# PS_2013v11.net
KiCad netlist of a schematic drawn in EAGLE
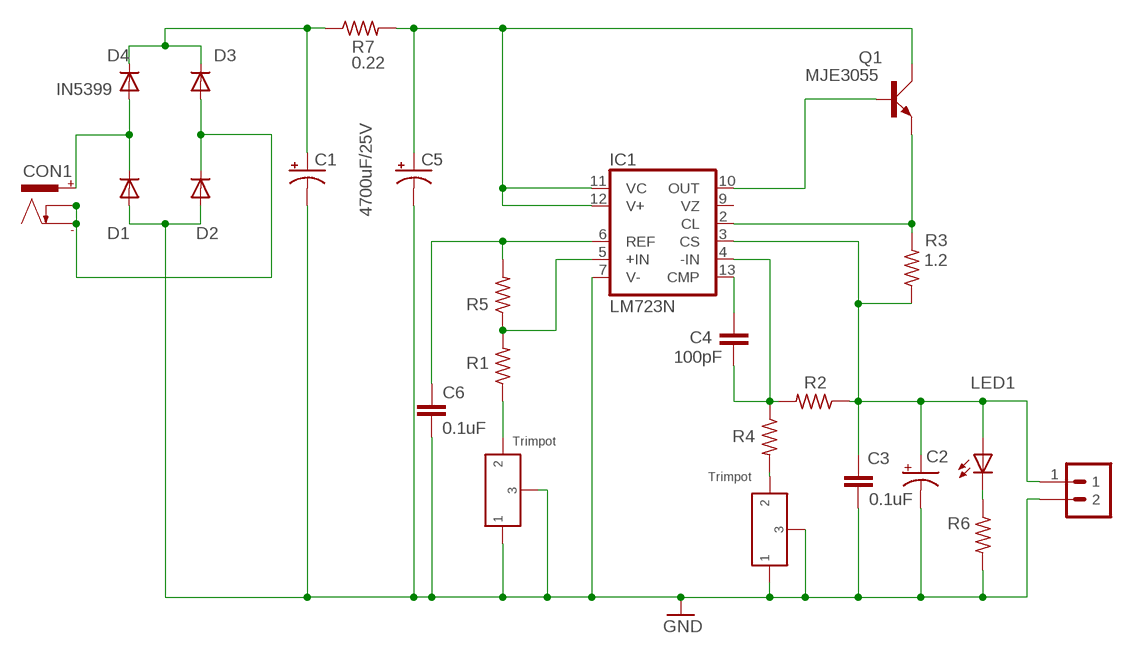
[diagram p0: schematic, sheet 1]

(export (version "E")
  (design (tool "Eeschema 10.0.6"))
  (components
    (comp (ref "C1")
      (value "CPOL-USE7.5-18")
      (footprint "eagle-import:E7,5-18")
      (libsource (lib "eagle-import") (part "CPOL-USE7.5-18"))
    )
    (comp (ref "C2")
      (value "CPOL-USE2,5-6E")
      (footprint "eagle-import:E2,5-6E")
      (libsource (lib "eagle-import") (part "CPOL-USE2,5-6E"))
    )
    (comp (ref "C3")
      (value "0.1uF")
      (footprint "eagle-import:C050-024X044")
      (libsource (lib "eagle-import") (part "C-EU050-024X044"))
    )
    (comp (ref "C4")
      (value "100pF")
      (footprint "eagle-import:C050-024X044")
      (libsource (lib "eagle-import") (part "C-EU050-024X044"))
    )
    (comp (ref "C5")
      (value "4700uF/25V")
      (footprint "eagle-import:E7,5-18")
      (libsource (lib "eagle-import") (part "CPOL-USE7.5-18"))
    )
    (comp (ref "C6")
      (value "0.1uF")
      (footprint "eagle-import:C050-024X044")
      (libsource (lib "eagle-import") (part "C-EU050-024X044"))
    )
    (comp (ref "CON1")
      (value "POWER_CON")
      (footprint "eagle-import:NEB21R")
      (libsource (lib "eagle-import") (part "POWER_CON"))
    )
    (comp (ref "D1")
      (value "IN5399")
      (footprint "eagle-import:DO15-12")
      (libsource (lib "eagle-import") (part "DIODE-DO15-12"))
    )
    (comp (ref "D2")
      (value "IN5399")
      (footprint "eagle-import:DO15-12")
      (libsource (lib "eagle-import") (part "DIODE-DO15-12"))
    )
    (comp (ref "D3")
      (value "IN5399")
      (footprint "eagle-import:DO15-12")
      (libsource (lib "eagle-import") (part "DIODE-DO15-12"))
    )
    (comp (ref "D4")
      (value "IN5399")
      (footprint "eagle-import:DO15-12")
      (libsource (lib "eagle-import") (part "DIODE-DO15-12"))
    )
    (comp (ref "IC1")
      (value "LM723N")
      (footprint "eagle-import:DIL14")
      (libsource (lib "eagle-import") (part "723NLM"))
    )
    (comp (ref "LED1")
      (value "LED3MM")
      (footprint "eagle-import:LED3MM")
      (libsource (lib "eagle-import") (part "LED3MM"))
    )
    (comp (ref "Q1")
      (value "MJE3055")
      (footprint "eagle-import:TO220AV")
      (libsource (lib "eagle-import") (part "MJE3055"))
    )
    (comp (ref "R1")
      (value "560k")
      (footprint "eagle-import:0204_5")
      (libsource (lib "eagle-import") (part "R-US_0204/5"))
    )
    (comp (ref "R2")
      (value "300k")
      (footprint "eagle-import:0204_5")
      (libsource (lib "eagle-import") (part "R-US_0204/5"))
    )
    (comp (ref "R3")
      (value "1.2")
      (footprint "eagle-import:0617_22")
      (libsource (lib "eagle-import") (part "R-US_0617/22"))
    )
    (comp (ref "R4")
      (value "300k")
      (footprint "eagle-import:0204_5")
      (libsource (lib "eagle-import") (part "R-US_0204/5"))
    )
    (comp (ref "R5")
      (value "220k")
      (footprint "eagle-import:0204_5")
      (libsource (lib "eagle-import") (part "R-US_0204/5"))
    )
    (comp (ref "R6")
      (value "330")
      (footprint "eagle-import:0204_5")
      (libsource (lib "eagle-import") (part "R-US_0204/5"))
    )
    (comp (ref "R7")
      (value "0.22")
      (footprint "eagle-import:0617_22")
      (libsource (lib "eagle-import") (part "R-US_0617/22"))
    )
    (comp (ref "U$1")
      (value "PRESET")
      (footprint "eagle-import:PRESET_PACK")
      (libsource (lib "eagle-import") (part "PRESET"))
    )
    (comp (ref "U$3")
      (value "PRESET")
      (footprint "eagle-import:PRESET_PACK")
      (libsource (lib "eagle-import") (part "PRESET"))
    )
    (comp (ref "U$4")
      (value "1X2_LR")
      (footprint "eagle-import:1X2_LR")
      (libsource (lib "eagle-import") (part "1X2_LR"))
    )
  )
  (nets
    (net (code "1") (name "GND") (class "Default")
      (node (ref "C1") (pin "-") (pinfunction "-_-") (pintype "passive"))
      (node (ref "C2") (pin "-") (pinfunction "-_-") (pintype "passive"))
      (node (ref "C3") (pin "2") (pinfunction "2_2") (pintype "passive"))
      (node (ref "C5") (pin "-") (pinfunction "-_-") (pintype "passive"))
      (node (ref "C6") (pin "2") (pinfunction "2_2") (pintype "passive"))
      (node (ref "D1") (pin "A") (pinfunction "A_A") (pintype "passive"))
      (node (ref "D2") (pin "A") (pinfunction "A_A") (pintype "passive"))
      (node (ref "IC1") (pin "7") (pinfunction "V-_7") (pintype "input"))
      (node (ref "R6") (pin "2") (pinfunction "2_2") (pintype "passive"))
      (node (ref "U$1") (pin "P$1") (pinfunction "1_P$1") (pintype "passive"))
      (node (ref "U$1") (pin "P$3") (pinfunction "3_P$3") (pintype "passive"))
      (node (ref "U$3") (pin "P$1") (pinfunction "1_P$1") (pintype "passive"))
      (node (ref "U$3") (pin "P$3") (pinfunction "3_P$3") (pintype "passive"))
      (node (ref "U$4") (pin "2") (pinfunction "2_2") (pintype "passive"))
    )
    (net (code "2") (name "Net-(C1-Pad+)") (class "Default")
      (node (ref "C1") (pin "+") (pinfunction "+_+") (pintype "passive"))
      (node (ref "D3") (pin "C") (pinfunction "C_C") (pintype "passive"))
      (node (ref "D4") (pin "C") (pinfunction "C_C") (pintype "passive"))
      (node (ref "R7") (pin "1") (pinfunction "1_1") (pintype "passive"))
    )
    (net (code "3") (name "Net-(CON1-Pad+)") (class "Default")
      (node (ref "CON1") (pin "+") (pinfunction "+_+") (pintype "passive"))
      (node (ref "D1") (pin "C") (pinfunction "C_C") (pintype "passive"))
      (node (ref "D4") (pin "A") (pinfunction "A_A") (pintype "passive"))
    )
    (net (code "4") (name "Net-(CON1-Pad-)") (class "Default")
      (node (ref "CON1") (pin "-") (pinfunction "-_-") (pintype "passive"))
      (node (ref "CON1") (pin "C") (pinfunction "C_C") (pintype "passive"))
      (node (ref "D2") (pin "C") (pinfunction "C_C") (pintype "passive"))
      (node (ref "D3") (pin "A") (pinfunction "A_A") (pintype "passive"))
    )
    (net (code "5") (name "Net-(IC1-+IN)") (class "Default")
      (node (ref "IC1") (pin "5") (pinfunction "+IN_5") (pintype "input"))
      (node (ref "R1") (pin "2") (pinfunction "2_2") (pintype "passive"))
      (node (ref "R5") (pin "1") (pinfunction "1_1") (pintype "passive"))
    )
    (net (code "6") (name "Net-(IC1--IN)") (class "Default")
      (node (ref "C4") (pin "2") (pinfunction "2_2") (pintype "passive"))
      (node (ref "IC1") (pin "4") (pinfunction "-IN_4") (pintype "input"))
      (node (ref "R2") (pin "2") (pinfunction "2_2") (pintype "passive"))
      (node (ref "R4") (pin "1") (pinfunction "1_1") (pintype "passive"))
    )
    (net (code "7") (name "Net-(IC1-CL)") (class "Default")
      (node (ref "IC1") (pin "2") (pinfunction "CL_2") (pintype "input"))
      (node (ref "Q1") (pin "E") (pinfunction "E_E") (pintype "passive"))
      (node (ref "R3") (pin "2") (pinfunction "2_2") (pintype "passive"))
    )
    (net (code "8") (name "Net-(IC1-CMP)") (class "Default")
      (node (ref "C4") (pin "1") (pinfunction "1_1") (pintype "passive"))
      (node (ref "IC1") (pin "13") (pinfunction "CMP_13") (pintype "passive"))
    )
    (net (code "9") (name "Net-(IC1-CS)") (class "Default")
      (node (ref "C2") (pin "+") (pinfunction "+_+") (pintype "passive"))
      (node (ref "C3") (pin "1") (pinfunction "1_1") (pintype "passive"))
      (node (ref "IC1") (pin "3") (pinfunction "CS_3") (pintype "input"))
      (node (ref "LED1") (pin "A") (pinfunction "A_A") (pintype "passive"))
      (node (ref "R2") (pin "1") (pinfunction "1_1") (pintype "passive"))
      (node (ref "R3") (pin "1") (pinfunction "1_1") (pintype "passive"))
      (node (ref "U$4") (pin "1") (pinfunction "1_1") (pintype "passive"))
    )
    (net (code "10") (name "Net-(IC1-OUT)") (class "Default")
      (node (ref "IC1") (pin "10") (pinfunction "OUT_10") (pintype "output"))
      (node (ref "Q1") (pin "B") (pinfunction "B_B") (pintype "passive"))
    )
    (net (code "11") (name "Net-(IC1-REF)") (class "Default")
      (node (ref "C6") (pin "1") (pinfunction "1_1") (pintype "passive"))
      (node (ref "IC1") (pin "6") (pinfunction "REF_6") (pintype "output"))
      (node (ref "R5") (pin "2") (pinfunction "2_2") (pintype "passive"))
    )
    (net (code "12") (name "Net-(IC1-V+)") (class "Default")
      (node (ref "C5") (pin "+") (pinfunction "+_+") (pintype "passive"))
      (node (ref "IC1") (pin "11") (pinfunction "VC_11") (pintype "input"))
      (node (ref "IC1") (pin "12") (pinfunction "V+_12") (pintype "input"))
      (node (ref "Q1") (pin "C") (pinfunction "C_C") (pintype "passive"))
      (node (ref "R7") (pin "2") (pinfunction "2_2") (pintype "passive"))
    )
    (net (code "13") (name "Net-(LED1-C)") (class "Default")
      (node (ref "LED1") (pin "K") (pinfunction "C_K") (pintype "passive"))
      (node (ref "R6") (pin "1") (pinfunction "1_1") (pintype "passive"))
    )
    (net (code "14") (name "Net-(U$1-2)") (class "Default")
      (node (ref "R1") (pin "1") (pinfunction "1_1") (pintype "passive"))
      (node (ref "U$1") (pin "P$2") (pinfunction "2_P$2") (pintype "passive"))
    )
    (net (code "15") (name "Net-(U$3-2)") (class "Default")
      (node (ref "R4") (pin "2") (pinfunction "2_2") (pintype "passive"))
      (node (ref "U$3") (pin "P$2") (pinfunction "2_P$2") (pintype "passive"))
    )
    (net (code "16") (name "unconnected-(IC1-VZ-Pad9)") (class "Default")
      (node (ref "IC1") (pin "9") (pinfunction "VZ_9") (pintype "output"))
    )
  )
)
